# QRE1113-3.net
KiCad netlist of a schematic drawn in Altium Designer
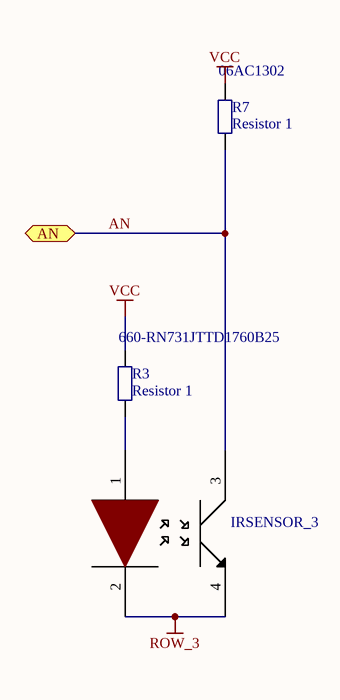
[diagram p0: QRE1113-3.SchDoc]

(export (version "E")
  (design (tool "Eeschema 10.0.6"))
  (components
    (comp (ref "IRSENSOR_3")
      (value "QRE1113GR")
      (footprint "QRE1113:QRE1113GR")
      (libsource (lib "Keyboard Library") (part "QRE1113GR"))
    )
    (comp (ref "R3")
      (value "Resistor 1")
      (footprint "R-0603")
      (description "Resistor")
      (fields (field (name "SUPPLIER PART NUMBER 1") "660-RN731JTTD1760B25"))
      (libsource (lib "Max Library") (part "Resistor 1"))
    )
    (comp (ref "R7")
      (value "Resistor 1")
      (footprint "R-0603")
      (description "Resistor")
      (fields (field (name "SUPPLIER PART NUMBER 1") "06AC1302"))
      (libsource (lib "") (part "Resistor 1_1"))
    )
  )
  (nets
    (net (code "1") (name "/AN") (class "Default")
      (node (ref "IRSENSOR_3") (pin "3") (pinfunction "3_3") (pintype "passive"))
      (node (ref "R7") (pin "2") (pinfunction "2_2") (pintype "passive"))
    )
    (net (code "2") (name "Net-(IRSENSOR_3-Pad1)") (class "Default")
      (node (ref "IRSENSOR_3") (pin "1") (pinfunction "1_1") (pintype "passive"))
      (node (ref "R3") (pin "1") (pinfunction "1_1") (pintype "passive"))
    )
    (net (code "3") (name "ROW_3") (class "Default")
      (node (ref "IRSENSOR_3") (pin "2") (pinfunction "2_2") (pintype "passive"))
      (node (ref "IRSENSOR_3") (pin "4") (pinfunction "4_4") (pintype "passive"))
    )
    (net (code "4") (name "VCC") (class "Default")
      (node (ref "R3") (pin "2") (pinfunction "2_2") (pintype "passive"))
      (node (ref "R7") (pin "1") (pinfunction "1_1") (pintype "passive"))
    )
  )
)
